# NOR_FLASH.net
KiCad netlist of a schematic drawn in Altium Designer
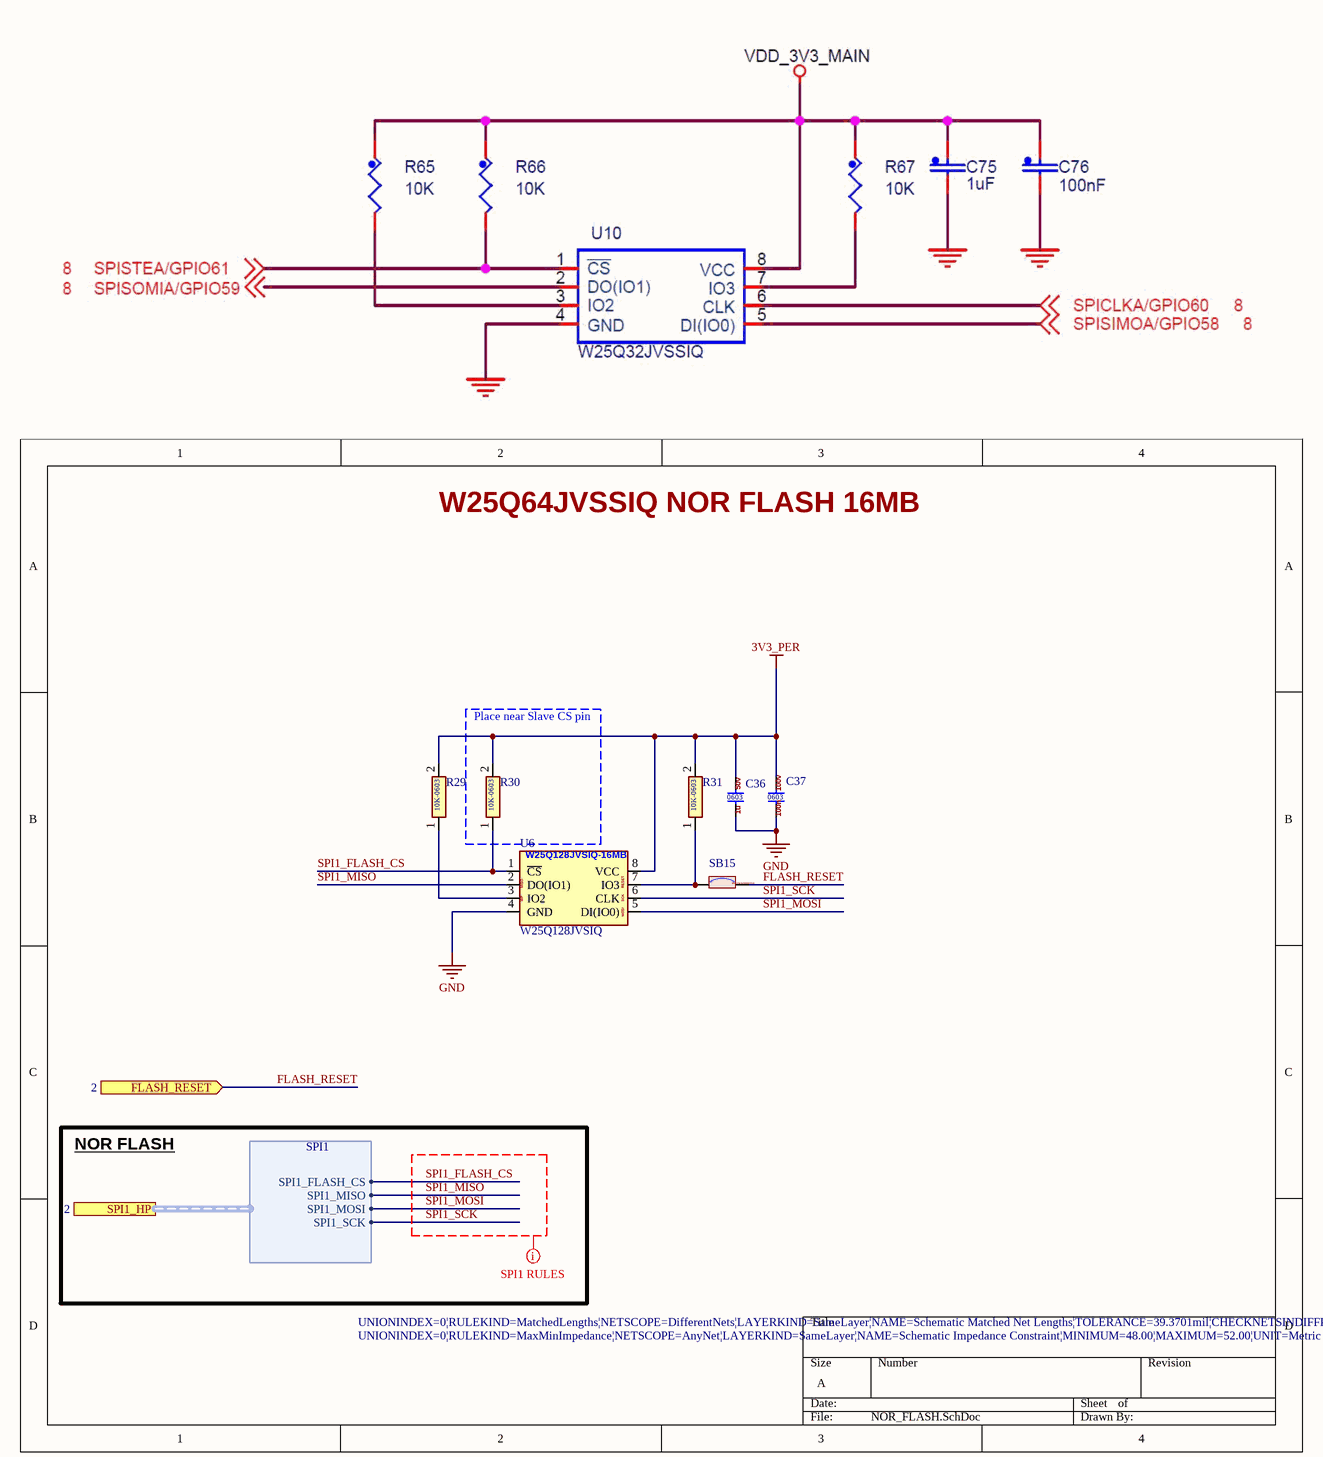
[diagram p0: NOR_FLASH.SchDoc]

(export (version "E")
  (design (tool "Eeschema 10.0.6"))
  (components
    (comp (ref "C36")
      (value "CL10A105KB8NNNC")
      (footprint "0603-CAP")
      (description "CAP: CER 1UF 50V X5R 0603")
      (fields (field (name "LCSC PART #") "C15849"))
      (libsource (lib "Nadim Altium Lib-Univ") (part "CL10A105KB8NNNC"))
    )
    (comp (ref "C37")
      (value "CL10B104KC8NNNC")
      (footprint "0603-CAP")
      (description "CAP: CER 100NF 100V X7R 0603")
      (fields (field (name "LCSC PART #") "C15725"))
      (libsource (lib "Nadim Altium Lib-Univ") (part "CL10B104KC8NNNC"))
    )
    (comp (ref "R29")
      (value "0603WAF1002T5E")
      (footprint "0603-RES")
      (description "RES: 10K OHM 1% 100mW 0603 75V")
      (fields (field (name "LCSC PART #") "C25804"))
      (libsource (lib "Nadim Altium Lib-Univ") (part "0603WAF1002T5E"))
    )
    (comp (ref "R30")
      (value "0603WAF1002T5E")
      (footprint "0603-RES")
      (description "RES: 10K OHM 1% 100mW 0603 75V")
      (fields (field (name "LCSC PART #") "C25804"))
      (libsource (lib "Nadim Altium Lib-Univ") (part "0603WAF1002T5E"))
    )
    (comp (ref "R31")
      (value "0603WAF1002T5E")
      (footprint "0603-RES")
      (description "RES: 10K OHM 1% 100mW 0603 75V")
      (fields (field (name "LCSC PART #") "C25804"))
      (libsource (lib "Nadim Altium Lib-Univ") (part "0603WAF1002T5E"))
    )
    (comp (ref "SB15")
      (value "0603WAF0000T5E")
      (footprint "SOLDER-BRIDGE_R0603-0R")
      (description "Solder Bridge: ON SB 0603")
      (fields (field (name "LCSC PART #") "C21189"))
      (libsource (lib "Nadim Altium Lib-Univ") (part "0603WAF0000T5E"))
    )
    (comp (ref "U6")
      (value "W25Q128JVSIQ")
      (footprint "Nadim Altium Lib-Univ:SOIC-8N")
      (description "Flash: 128Mbit SPI 133MHz SOIC-8-208mil NOR FLASH ROHS")
      (fields (field (name "LCSC PART #") "C97521"))
      (libsource (lib "Nadim Altium Lib-Univ") (part "W25Q128JVSIQ"))
    )
  )
  (nets
    (net (code "2") (name "/FLASH_RESET") (class "Default")
      (node (ref "SB15") (pin "1") (pinfunction "1_1") (pintype "passive"))
    )
    (net (code "3") (name "/SPI1_FLASH_CS") (class "Default")
      (node (ref "R30") (pin "1") (pinfunction "1_1") (pintype "passive"))
      (node (ref "U6") (pin "1") (pinfunction "~{CS}_1") (pintype "passive"))
    )
    (net (code "4") (name "/SPI1_MISO") (class "Default")
      (node (ref "U6") (pin "2") (pinfunction "DO(IO1)_2") (pintype "passive"))
    )
    (net (code "5") (name "/SPI1_MOSI") (class "Default")
      (node (ref "U6") (pin "5") (pinfunction "DI(IO0)_5") (pintype "passive"))
    )
    (net (code "6") (name "/SPI1_SCK") (class "Default")
      (node (ref "U6") (pin "6") (pinfunction "CLK_6") (pintype "passive"))
    )
    (net (code "8") (name "3V3_PER") (class "Default")
      (node (ref "C36") (pin "2") (pinfunction "2_2") (pintype "passive"))
      (node (ref "C37") (pin "2") (pinfunction "2_2") (pintype "passive"))
      (node (ref "R29") (pin "2") (pinfunction "2_2") (pintype "passive"))
      (node (ref "R30") (pin "2") (pinfunction "2_2") (pintype "passive"))
      (node (ref "R31") (pin "2") (pinfunction "2_2") (pintype "passive"))
      (node (ref "U6") (pin "8") (pinfunction "VCC_8") (pintype "passive"))
    )
    (net (code "9") (name "GND") (class "Default")
      (node (ref "C36") (pin "1") (pinfunction "1_1") (pintype "passive"))
      (node (ref "C37") (pin "1") (pinfunction "1_1") (pintype "passive"))
      (node (ref "U6") (pin "4") (pinfunction "GND_4") (pintype "passive"))
    )
    (net (code "10") (name "Net-(U6-IO2)") (class "Default")
      (node (ref "R29") (pin "1") (pinfunction "1_1") (pintype "passive"))
      (node (ref "U6") (pin "3") (pinfunction "IO2_3") (pintype "passive"))
    )
    (net (code "11") (name "Net-(U6-IO3)") (class "Default")
      (node (ref "R31") (pin "1") (pinfunction "1_1") (pintype "passive"))
      (node (ref "SB15") (pin "2") (pinfunction "2_2") (pintype "passive"))
      (node (ref "U6") (pin "7") (pinfunction "IO3_7") (pintype "passive"))
    )
  )
)
